# Sensor.net
KiCad netlist of a schematic drawn in Altium Designer
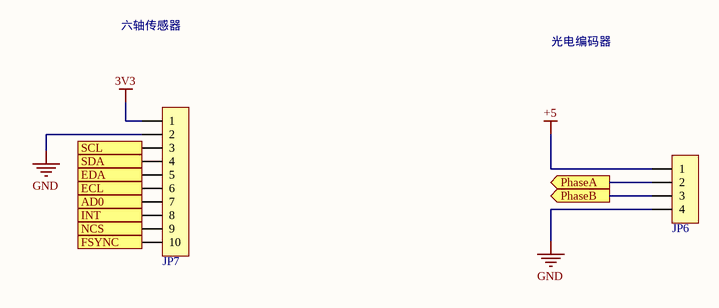
[diagram p0: Sensor.SchDoc]

(export (version "E")
  (design (tool "Eeschema 10.0.6"))
  (components
    (comp (ref "JP6")
      (value "HDR-1X4")
      (footprint "KF350-4P")
      (description "4P接插件")
      (fields (field (name "版权归属") "源创客"))
      (libsource (lib "4.6   - 接插件-脚距3.5") (part "Header 4"))
    )
    (comp (ref "JP7")
      (value "HDR-1X10")
      (footprint "HDR2.54-LI-10P")
      (description "10P接插件")
      (fields (field (name "版权归属") "源创客"))
      (libsource (lib "4.5   - 接插件-脚距2.54") (part "Header 10"))
    )
  )
  (nets
    (net (code "1") (name "+5") (class "Default")
      (node (ref "JP6") (pin "1") (pinfunction "1_1") (pintype "passive"))
    )
    (net (code "2") (name "/AD0") (class "Default")
      (node (ref "JP7") (pin "7") (pinfunction "7_7") (pintype "passive"))
    )
    (net (code "3") (name "/ECL") (class "Default")
      (node (ref "JP7") (pin "6") (pinfunction "6_6") (pintype "passive"))
    )
    (net (code "4") (name "/EDA") (class "Default")
      (node (ref "JP7") (pin "5") (pinfunction "5_5") (pintype "passive"))
    )
    (net (code "5") (name "/FSYNC") (class "Default")
      (node (ref "JP7") (pin "10") (pinfunction "10_10") (pintype "passive"))
    )
    (net (code "6") (name "/INT") (class "Default")
      (node (ref "JP7") (pin "8") (pinfunction "8_8") (pintype "passive"))
    )
    (net (code "7") (name "/NCS") (class "Default")
      (node (ref "JP7") (pin "9") (pinfunction "9_9") (pintype "passive"))
    )
    (net (code "8") (name "/PhaseA") (class "Default")
      (node (ref "JP6") (pin "2") (pinfunction "2_2") (pintype "passive"))
    )
    (net (code "9") (name "/PhaseB") (class "Default")
      (node (ref "JP6") (pin "3") (pinfunction "3_3") (pintype "passive"))
    )
    (net (code "10") (name "/SCL") (class "Default")
      (node (ref "JP7") (pin "3") (pinfunction "3_3") (pintype "passive"))
    )
    (net (code "11") (name "/SDA") (class "Default")
      (node (ref "JP7") (pin "4") (pinfunction "4_4") (pintype "passive"))
    )
    (net (code "12") (name "3V3") (class "Default")
      (node (ref "JP7") (pin "1") (pinfunction "1_1") (pintype "passive"))
    )
    (net (code "13") (name "GND") (class "Default")
      (node (ref "JP6") (pin "4") (pinfunction "4_4") (pintype "passive"))
      (node (ref "JP7") (pin "2") (pinfunction "2_2") (pintype "passive"))
    )
  )
)
